# Sheet1.net
KiCad netlist of a schematic drawn in Altium Designer
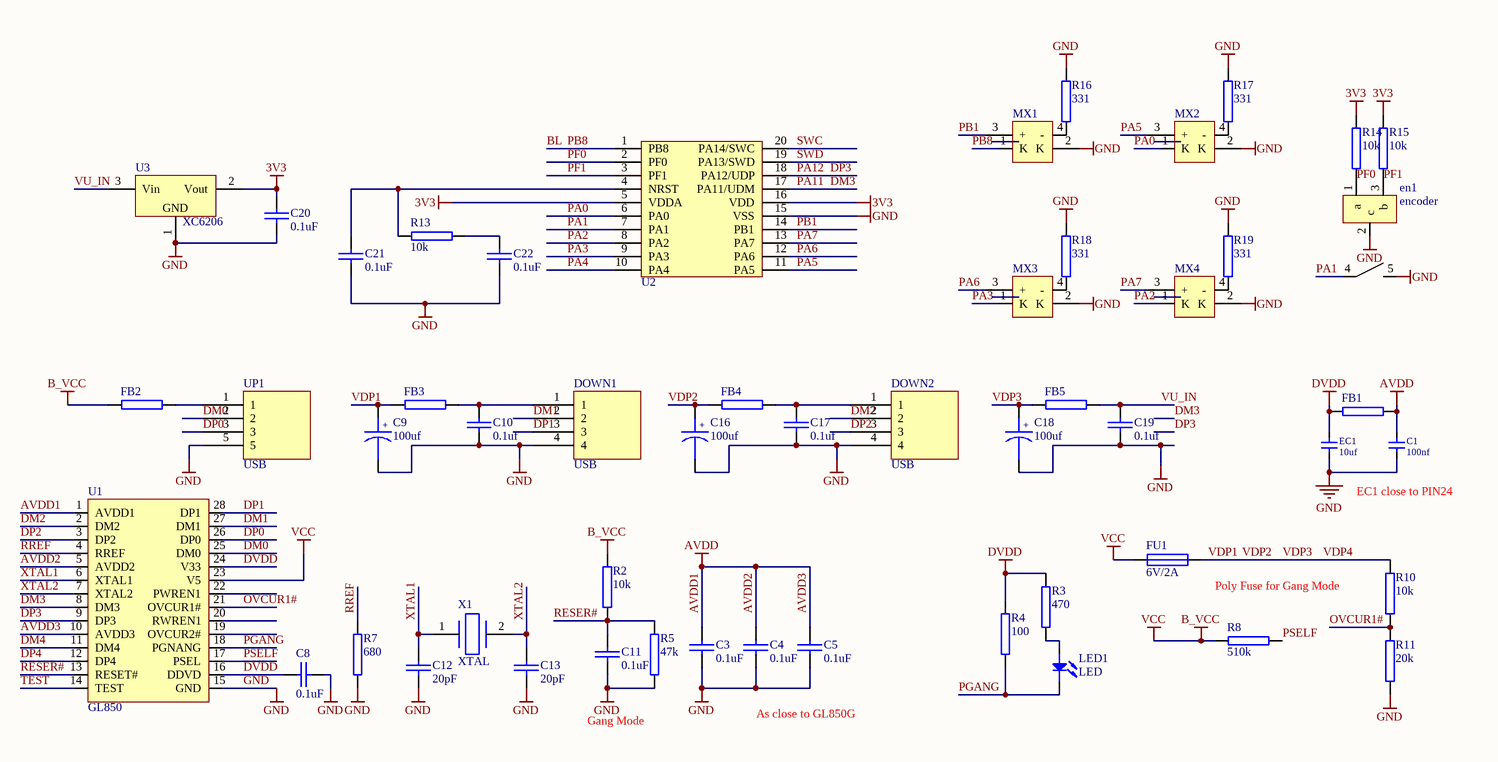
[diagram p0: Sheet1.SchDoc]

(export (version "E")
  (design (tool "Eeschema 10.0.6"))
  (components
    (comp (ref "C1")
      (value "100nf")
      (footprint "C0805")
      (description "Capacitor")
      (libsource (lib "lflj_com") (part "CAP"))
    )
    (comp (ref "C3") (value "0.1uF") (footprint "C0805") (libsource (lib "常用元件库") (part "CAP")))
    (comp (ref "C4") (value "0.1uF") (footprint "C0805") (libsource (lib "常用元件库") (part "CAP")))
    (comp (ref "C5") (value "0.1uF") (footprint "C0805") (libsource (lib "常用元件库") (part "CAP")))
    (comp (ref "C8") (value "0.1uF") (footprint "C0805") (libsource (lib "常用元件库") (part "CAP")))
    (comp (ref "C9")
      (value "100uf")
      (footprint "C0805")
      (description "Capacitor")
      (libsource (lib "元件库") (part "电解电容"))
    )
    (comp (ref "C10") (value "0.1uf") (footprint "C0805") (libsource (lib "元件库") (part "CAP")))
    (comp (ref "C11") (value "0.1uF") (footprint "C0805") (libsource (lib "常用元件库") (part "CAP")))
    (comp (ref "C12") (value "20pF") (footprint "C0805") (libsource (lib "常用元件库") (part "CAP")))
    (comp (ref "C13") (value "20pF") (footprint "C0805") (libsource (lib "常用元件库") (part "CAP")))
    (comp (ref "C16")
      (value "100uf")
      (footprint "C0805")
      (description "Capacitor")
      (libsource (lib "元件库") (part "电解电容"))
    )
    (comp (ref "C17") (value "0.1uf") (footprint "C0805") (libsource (lib "元件库") (part "CAP")))
    (comp (ref "C18")
      (value "100uf")
      (footprint "C0805")
      (description "Capacitor")
      (libsource (lib "元件库") (part "电解电容"))
    )
    (comp (ref "C19") (value "0.1uf") (footprint "C0805") (libsource (lib "元件库") (part "CAP")))
    (comp (ref "C20") (value "0.1uF") (footprint "C0805") (libsource (lib "常用元件库") (part "CAP")))
    (comp (ref "C21") (value "0.1uF") (footprint "C0805") (libsource (lib "常用元件库") (part "CAP")))
    (comp (ref "C22") (value "0.1uF") (footprint "C0805") (libsource (lib "常用元件库") (part "CAP")))
    (comp (ref "DOWN1")
      (value "USB")
      (footprint "USB-A/S_D")
      (description "4 Pin Header")
      (libsource (lib "元件库") (part "USB"))
    )
    (comp (ref "DOWN2")
      (value "USB")
      (footprint "USB-A/S_D")
      (description "4 Pin Header")
      (libsource (lib "元件库") (part "USB"))
    )
    (comp (ref "EC1")
      (value "10uf")
      (footprint "C0805")
      (description "Capacitor")
      (libsource (lib "lflj_com") (part "CAP"))
    )
    (comp (ref "en1")
      (value "encoder")
      (footprint "RES ADJ-EC12")
      (libsource (lib "KeyBoard(1)") (part "encoder"))
    )
    (comp (ref "FB1") (value "~") (footprint "R0805") (libsource (lib "元件库") (part "R")))
    (comp (ref "FB2") (value "~") (footprint "R0805") (libsource (lib "元件库") (part "R")))
    (comp (ref "FB3") (value "~") (footprint "R0805") (libsource (lib "元件库") (part "R")))
    (comp (ref "FB4") (value "~") (footprint "R0805") (libsource (lib "元件库") (part "R")))
    (comp (ref "FB5") (value "~") (footprint "R0805") (libsource (lib "元件库") (part "R")))
    (comp (ref "FU1") (value "6V/2A") (footprint "FUSE-F1210") (libsource (lib "元件库") (part "FUSE")))
    (comp (ref "LED1") (value "LED") (footprint "LED0805") (libsource (lib "常用元件库") (part "LED")))
    (comp (ref "MX1") (value "~") (footprint "MX_SW-5") (libsource (lib "KeyBoard(1)") (part "MX_SW-7")))
    (comp (ref "MX2") (value "~") (footprint "MX_SW-5") (libsource (lib "KeyBoard(1)") (part "MX_SW-7")))
    (comp (ref "MX3") (value "~") (footprint "MX_SW-5") (libsource (lib "KeyBoard(1)") (part "MX_SW-7")))
    (comp (ref "MX4") (value "~") (footprint "MX_SW-5") (libsource (lib "KeyBoard(1)") (part "MX_SW-7")))
    (comp (ref "R2") (value "10k") (footprint "R0805") (libsource (lib "常用元件库") (part "RES")))
    (comp (ref "R3") (value "470") (footprint "R0805") (libsource (lib "常用元件库") (part "RES")))
    (comp (ref "R4") (value "100") (footprint "R0805") (libsource (lib "常用元件库") (part "RES")))
    (comp (ref "R5") (value "47k") (footprint "R0805") (libsource (lib "常用元件库") (part "RES")))
    (comp (ref "R7") (value "680") (footprint "R0805") (libsource (lib "常用元件库") (part "RES")))
    (comp (ref "R8") (value "510k") (footprint "R0805") (libsource (lib "元件库") (part "R")))
    (comp (ref "R10") (value "10k") (footprint "R0805") (libsource (lib "元件库") (part "R")))
    (comp (ref "R11") (value "20k") (footprint "R0805") (libsource (lib "元件库") (part "R")))
    (comp (ref "R13") (value "10k") (footprint "R0805") (libsource (lib "常用元件库") (part "RES")))
    (comp (ref "R14") (value "10k") (footprint "R0805") (libsource (lib "常用元件库") (part "RES")))
    (comp (ref "R15") (value "10k") (footprint "R0805") (libsource (lib "常用元件库") (part "RES")))
    (comp (ref "R16") (value "331") (footprint "R0805") (libsource (lib "KeyBoard(1)") (part "R")))
    (comp (ref "R17") (value "331") (footprint "R0805") (libsource (lib "KeyBoard(1)") (part "R")))
    (comp (ref "R18") (value "331") (footprint "R0805") (libsource (lib "KeyBoard(1)") (part "R")))
    (comp (ref "R19") (value "331") (footprint "R0805") (libsource (lib "KeyBoard(1)") (part "R")))
    (comp (ref "U1") (value "GL850") (footprint "SSOP28") (libsource (lib "SCHL") (part "GL850")))
    (comp (ref "U2")
      (value "stm32f042Fx")
      (footprint "TSSOP20")
      (libsource (lib "KeyBoard(1)") (part "stm32f042Fx"))
    )
    (comp (ref "U3") (value "XC6206") (footprint "SOT23-3") (libsource (lib "KeyBoard(1)") (part "XC6206")))
    (comp (ref "UP1")
      (value "USB")
      (footprint "USB-micro_B")
      (description "4 Pin Header")
      (libsource (lib "") (part "USB_1"))
    )
    (comp (ref "X1")
      (value "XTAL")
      (footprint "X5032")
      (description "12M")
      (libsource (lib "元件库") (part "XTAL"))
    )
  )
  (nets
    (net (code "1") (name "/BL") (class "Default")
      (node (ref "MX1") (pin "1") (pinfunction "K_1") (pintype "passive"))
      (node (ref "U2") (pin "1") (pinfunction "PB8_1") (pintype "passive"))
    )
    (net (code "2") (name "/DM0") (class "Default")
      (node (ref "U1") (pin "25") (pinfunction "DM0_25") (pintype "passive"))
      (node (ref "UP1") (pin "2") (pinfunction "2_2") (pintype "passive"))
    )
    (net (code "3") (name "/DM1") (class "Default")
      (node (ref "DOWN1") (pin "2") (pinfunction "2_2") (pintype "passive"))
      (node (ref "U1") (pin "27") (pinfunction "DM1_27") (pintype "passive"))
    )
    (net (code "4") (name "/DM2") (class "Default")
      (node (ref "DOWN2") (pin "2") (pinfunction "2_2") (pintype "passive"))
      (node (ref "U1") (pin "2") (pinfunction "DM2_2") (pintype "passive"))
    )
    (net (code "5") (name "/DM3") (class "Default")
      (node (ref "U1") (pin "8") (pinfunction "DM3_8") (pintype "passive"))
      (node (ref "U2") (pin "17") (pinfunction "PA11/UDM_17") (pintype "passive"))
    )
    (net (code "6") (name "/DM4") (class "Default")
      (node (ref "U1") (pin "11") (pinfunction "DM4_11") (pintype "passive"))
    )
    (net (code "7") (name "/DP0") (class "Default")
      (node (ref "U1") (pin "26") (pinfunction "DP0_26") (pintype "passive"))
      (node (ref "UP1") (pin "3") (pinfunction "3_3") (pintype "passive"))
    )
    (net (code "8") (name "/DP1") (class "Default")
      (node (ref "DOWN1") (pin "3") (pinfunction "3_3") (pintype "passive"))
      (node (ref "U1") (pin "28") (pinfunction "DP1_28") (pintype "passive"))
    )
    (net (code "9") (name "/DP2") (class "Default")
      (node (ref "DOWN2") (pin "3") (pinfunction "3_3") (pintype "passive"))
      (node (ref "U1") (pin "3") (pinfunction "DP2_3") (pintype "passive"))
    )
    (net (code "10") (name "/DP3") (class "Default")
      (node (ref "U1") (pin "9") (pinfunction "DP3_9") (pintype "passive"))
      (node (ref "U2") (pin "18") (pinfunction "PA12/UDP_18") (pintype "passive"))
    )
    (net (code "11") (name "/DP4") (class "Default")
      (node (ref "U1") (pin "12") (pinfunction "DP4_12") (pintype "passive"))
    )
    (net (code "12") (name "/OVCUR1#") (class "Default")
      (node (ref "R10") (pin "1") (pinfunction "1_1") (pintype "passive"))
      (node (ref "R11") (pin "2") (pinfunction "2_2") (pintype "passive"))
      (node (ref "U1") (pin "21") (pinfunction "OVCUR1#_21") (pintype "passive"))
    )
    (net (code "13") (name "/PA0") (class "Default")
      (node (ref "MX2") (pin "1") (pinfunction "K_1") (pintype "passive"))
      (node (ref "U2") (pin "6") (pinfunction "PA0_6") (pintype "passive"))
    )
    (net (code "14") (name "/PA1") (class "Default")
      (node (ref "U2") (pin "7") (pinfunction "PA1_7") (pintype "passive"))
      (node (ref "en1") (pin "4") (pintype "passive"))
    )
    (net (code "15") (name "/PA2") (class "Default")
      (node (ref "MX4") (pin "1") (pinfunction "K_1") (pintype "passive"))
      (node (ref "U2") (pin "8") (pinfunction "PA2_8") (pintype "passive"))
    )
    (net (code "16") (name "/PA3") (class "Default")
      (node (ref "MX3") (pin "1") (pinfunction "K_1") (pintype "passive"))
      (node (ref "U2") (pin "9") (pinfunction "PA3_9") (pintype "passive"))
    )
    (net (code "17") (name "/PA4") (class "Default")
      (node (ref "U2") (pin "10") (pinfunction "PA4_10") (pintype "passive"))
    )
    (net (code "18") (name "/PA5") (class "Default")
      (node (ref "MX2") (pin "3") (pinfunction "+_3") (pintype "passive"))
      (node (ref "U2") (pin "11") (pinfunction "PA5_11") (pintype "passive"))
    )
    (net (code "19") (name "/PA6") (class "Default")
      (node (ref "MX3") (pin "3") (pinfunction "+_3") (pintype "passive"))
      (node (ref "U2") (pin "12") (pinfunction "PA6_12") (pintype "passive"))
    )
    (net (code "20") (name "/PA7") (class "Default")
      (node (ref "MX4") (pin "3") (pinfunction "+_3") (pintype "passive"))
      (node (ref "U2") (pin "13") (pinfunction "PA7_13") (pintype "passive"))
    )
    (net (code "21") (name "/PB1") (class "Default")
      (node (ref "MX1") (pin "3") (pinfunction "+_3") (pintype "passive"))
      (node (ref "U2") (pin "14") (pinfunction "PB1_14") (pintype "passive"))
    )
    (net (code "22") (name "/PF0") (class "Default")
      (node (ref "R14") (pin "1") (pinfunction "1_1") (pintype "passive"))
      (node (ref "U2") (pin "2") (pinfunction "PF0_2") (pintype "passive"))
      (node (ref "en1") (pin "1") (pinfunction "a_1") (pintype "passive"))
    )
    (net (code "23") (name "/PF1") (class "Default")
      (node (ref "R15") (pin "1") (pinfunction "1_1") (pintype "passive"))
      (node (ref "U2") (pin "3") (pinfunction "PF1_3") (pintype "passive"))
      (node (ref "en1") (pin "3") (pinfunction "b_3") (pintype "passive"))
    )
    (net (code "24") (name "/PGANG") (class "Default")
      (node (ref "LED1") (pin "2") (pinfunction "2_2") (pintype "passive"))
      (node (ref "R4") (pin "1") (pinfunction "1_1") (pintype "passive"))
      (node (ref "U1") (pin "18") (pinfunction "PGNANG_18") (pintype "passive"))
    )
    (net (code "25") (name "/PSELF") (class "Default")
      (node (ref "R8") (pin "2") (pinfunction "2_2") (pintype "passive"))
      (node (ref "U1") (pin "17") (pinfunction "PSEL_17") (pintype "passive"))
    )
    (net (code "26") (name "/RESER#") (class "Default")
      (node (ref "C11") (pin "1") (pinfunction "1_1") (pintype "passive"))
      (node (ref "R2") (pin "1") (pinfunction "1_1") (pintype "passive"))
      (node (ref "R5") (pin "1") (pinfunction "1_1") (pintype "passive"))
      (node (ref "U1") (pin "13") (pinfunction "RESET#_13") (pintype "passive"))
    )
    (net (code "27") (name "/RREF") (class "Default")
      (node (ref "R7") (pin "2") (pinfunction "2_2") (pintype "passive"))
      (node (ref "U1") (pin "4") (pinfunction "RREF_4") (pintype "passive"))
    )
    (net (code "28") (name "/SWC") (class "Default")
      (node (ref "U2") (pin "20") (pinfunction "PA14/SWC_20") (pintype "passive"))
    )
    (net (code "29") (name "/SWD") (class "Default")
      (node (ref "U2") (pin "19") (pinfunction "PA13/SWD_19") (pintype "passive"))
    )
    (net (code "30") (name "/TEST") (class "Default")
      (node (ref "U1") (pin "14") (pinfunction "TEST_14") (pintype "passive"))
    )
    (net (code "31") (name "/VDP1") (class "Default")
      (node (ref "C16") (pin "1") (pinfunction "1_1") (pintype "passive"))
      (node (ref "C18") (pin "1") (pinfunction "1_1") (pintype "passive"))
      (node (ref "C9") (pin "1") (pinfunction "1_1") (pintype "passive"))
      (node (ref "FB3") (pin "1") (pinfunction "1_1") (pintype "passive"))
      (node (ref "FB4") (pin "1") (pinfunction "1_1") (pintype "passive"))
      (node (ref "FB5") (pin "1") (pinfunction "1_1") (pintype "passive"))
      (node (ref "FU1") (pin "2") (pinfunction "2_2") (pintype "passive"))
      (node (ref "R10") (pin "2") (pinfunction "2_2") (pintype "passive"))
    )
    (net (code "32") (name "/VU_IN") (class "Default")
      (node (ref "C19") (pin "1") (pinfunction "1_1") (pintype "passive"))
      (node (ref "FB5") (pin "2") (pinfunction "2_2") (pintype "passive"))
      (node (ref "U3") (pin "3") (pinfunction "Vin_3") (pintype "passive"))
    )
    (net (code "33") (name "/XTAL1") (class "Default")
      (node (ref "C12") (pin "2") (pinfunction "2_2") (pintype "passive"))
      (node (ref "U1") (pin "6") (pinfunction "XTAL1_6") (pintype "passive"))
      (node (ref "X1") (pin "1") (pinfunction "1_1") (pintype "passive"))
    )
    (net (code "34") (name "/XTAL2") (class "Default")
      (node (ref "C13") (pin "2") (pinfunction "2_2") (pintype "passive"))
      (node (ref "U1") (pin "7") (pinfunction "XTAL2_7") (pintype "passive"))
      (node (ref "X1") (pin "2") (pinfunction "2_2") (pintype "passive"))
    )
    (net (code "35") (name "3V3") (class "Default")
      (node (ref "C20") (pin "1") (pinfunction "1_1") (pintype "passive"))
      (node (ref "R14") (pin "2") (pinfunction "2_2") (pintype "passive"))
      (node (ref "R15") (pin "2") (pinfunction "2_2") (pintype "passive"))
      (node (ref "U2") (pin "16") (pinfunction "VDD_16") (pintype "passive"))
      (node (ref "U2") (pin "5") (pinfunction "VDDA_5") (pintype "passive"))
      (node (ref "U3") (pin "2") (pinfunction "Vout_2") (pintype "passive"))
    )
    (net (code "36") (name "AVDD") (class "Default")
      (node (ref "C1") (pin "2") (pinfunction "2_2") (pintype "passive"))
      (node (ref "C3") (pin "1") (pinfunction "1_1") (pintype "passive"))
      (node (ref "C4") (pin "1") (pinfunction "1_1") (pintype "passive"))
      (node (ref "C5") (pin "1") (pinfunction "1_1") (pintype "passive"))
      (node (ref "FB1") (pin "2") (pinfunction "2_2") (pintype "passive"))
      (node (ref "U1") (pin "1") (pinfunction "AVDD1_1") (pintype "passive"))
      (node (ref "U1") (pin "10") (pinfunction "AVDD3_10") (pintype "passive"))
      (node (ref "U1") (pin "5") (pinfunction "AVDD2_5") (pintype "passive"))
    )
    (net (code "37") (name "B_VCC") (class "Default")
      (node (ref "FB2") (pin "1") (pinfunction "1_1") (pintype "passive"))
      (node (ref "FU1") (pin "1") (pinfunction "1_1") (pintype "passive"))
      (node (ref "R2") (pin "2") (pinfunction "2_2") (pintype "passive"))
      (node (ref "R8") (pin "1") (pinfunction "1_1") (pintype "passive"))
      (node (ref "U1") (pin "23") (pinfunction "V5_23") (pintype "passive"))
    )
    (net (code "38") (name "DVDD") (class "Default")
      (node (ref "C8") (pin "1") (pinfunction "1_1") (pintype "passive"))
      (node (ref "EC1") (pin "2") (pinfunction "2_2") (pintype "passive"))
      (node (ref "FB1") (pin "1") (pinfunction "1_1") (pintype "passive"))
      (node (ref "R3") (pin "2") (pinfunction "2_2") (pintype "passive"))
      (node (ref "R4") (pin "2") (pinfunction "2_2") (pintype "passive"))
      (node (ref "U1") (pin "16") (pinfunction "DDVD_16") (pintype "passive"))
      (node (ref "U1") (pin "24") (pinfunction "V33_24") (pintype "passive"))
    )
    (net (code "39") (name "GND") (class "Default")
      (node (ref "C1") (pin "1") (pinfunction "1_1") (pintype "passive"))
      (node (ref "C10") (pin "2") (pinfunction "2_2") (pintype "passive"))
      (node (ref "C11") (pin "2") (pinfunction "2_2") (pintype "passive"))
      (node (ref "C12") (pin "1") (pinfunction "1_1") (pintype "passive"))
      (node (ref "C13") (pin "1") (pinfunction "1_1") (pintype "passive"))
      (node (ref "C16") (pin "2") (pinfunction "2_2") (pintype "passive"))
      (node (ref "C17") (pin "2") (pinfunction "2_2") (pintype "passive"))
      (node (ref "C18") (pin "2") (pinfunction "2_2") (pintype "passive"))
      (node (ref "C19") (pin "2") (pinfunction "2_2") (pintype "passive"))
      (node (ref "C20") (pin "2") (pinfunction "2_2") (pintype "passive"))
      (node (ref "C21") (pin "1") (pinfunction "1_1") (pintype "passive"))
      (node (ref "C22") (pin "1") (pinfunction "1_1") (pintype "passive"))
      (node (ref "C3") (pin "2") (pinfunction "2_2") (pintype "passive"))
      (node (ref "C4") (pin "2") (pinfunction "2_2") (pintype "passive"))
      (node (ref "C5") (pin "2") (pinfunction "2_2") (pintype "passive"))
      (node (ref "C8") (pin "2") (pinfunction "2_2") (pintype "passive"))
      (node (ref "C9") (pin "2") (pinfunction "2_2") (pintype "passive"))
      (node (ref "DOWN1") (pin "4") (pinfunction "4_4") (pintype "passive"))
      (node (ref "DOWN2") (pin "4") (pinfunction "4_4") (pintype "passive"))
      (node (ref "EC1") (pin "1") (pinfunction "1_1") (pintype "passive"))
      (node (ref "MX1") (pin "2") (pinfunction "K_2") (pintype "passive"))
      (node (ref "MX2") (pin "2") (pinfunction "K_2") (pintype "passive"))
      (node (ref "MX3") (pin "2") (pinfunction "K_2") (pintype "passive"))
      (node (ref "MX4") (pin "2") (pinfunction "K_2") (pintype "passive"))
      (node (ref "R11") (pin "1") (pinfunction "1_1") (pintype "passive"))
      (node (ref "R16") (pin "2") (pinfunction "2_2") (pintype "passive"))
      (node (ref "R17") (pin "2") (pinfunction "2_2") (pintype "passive"))
      (node (ref "R18") (pin "2") (pinfunction "2_2") (pintype "passive"))
      (node (ref "R19") (pin "2") (pinfunction "2_2") (pintype "passive"))
      (node (ref "R5") (pin "2") (pinfunction "2_2") (pintype "passive"))
      (node (ref "R7") (pin "1") (pinfunction "1_1") (pintype "passive"))
      (node (ref "U1") (pin "15") (pinfunction "GND_15") (pintype "passive"))
      (node (ref "U2") (pin "15") (pinfunction "VSS_15") (pintype "passive"))
      (node (ref "U3") (pin "1") (pinfunction "GND_1") (pintype "passive"))
      (node (ref "UP1") (pin "5") (pinfunction "5_5") (pintype "passive"))
      (node (ref "en1") (pin "2") (pinfunction "c_2") (pintype "passive"))
      (node (ref "en1") (pin "5") (pintype "passive"))
    )
    (net (code "40") (name "Net-(C10-Pad1)") (class "Default")
      (node (ref "C10") (pin "1") (pinfunction "1_1") (pintype "passive"))
      (node (ref "DOWN1") (pin "1") (pinfunction "1_1") (pintype "passive"))
      (node (ref "FB3") (pin "2") (pinfunction "2_2") (pintype "passive"))
    )
    (net (code "41") (name "Net-(C17-Pad1)") (class "Default")
      (node (ref "C17") (pin "1") (pinfunction "1_1") (pintype "passive"))
      (node (ref "DOWN2") (pin "1") (pinfunction "1_1") (pintype "passive"))
      (node (ref "FB4") (pin "2") (pinfunction "2_2") (pintype "passive"))
    )
    (net (code "42") (name "Net-(C22-Pad2)") (class "Default")
      (node (ref "C22") (pin "2") (pinfunction "2_2") (pintype "passive"))
      (node (ref "R13") (pin "2") (pinfunction "2_2") (pintype "passive"))
    )
    (net (code "43") (name "Net-(FB2-Pad2)") (class "Default")
      (node (ref "FB2") (pin "2") (pinfunction "2_2") (pintype "passive"))
      (node (ref "UP1") (pin "1") (pinfunction "1_1") (pintype "passive"))
    )
    (net (code "44") (name "Net-(LED1-Pad1)") (class "Default")
      (node (ref "LED1") (pin "1") (pinfunction "1_1") (pintype "passive"))
      (node (ref "R3") (pin "1") (pinfunction "1_1") (pintype "passive"))
    )
    (net (code "45") (name "Net-(MX1--)") (class "Default")
      (node (ref "MX1") (pin "4") (pinfunction "-_4") (pintype "passive"))
      (node (ref "R16") (pin "1") (pinfunction "1_1") (pintype "passive"))
    )
    (net (code "46") (name "Net-(MX2--)") (class "Default")
      (node (ref "MX2") (pin "4") (pinfunction "-_4") (pintype "passive"))
      (node (ref "R17") (pin "1") (pinfunction "1_1") (pintype "passive"))
    )
    (net (code "47") (name "Net-(MX3--)") (class "Default")
      (node (ref "MX3") (pin "4") (pinfunction "-_4") (pintype "passive"))
      (node (ref "R18") (pin "1") (pinfunction "1_1") (pintype "passive"))
    )
    (net (code "48") (name "Net-(MX4--)") (class "Default")
      (node (ref "MX4") (pin "4") (pinfunction "-_4") (pintype "passive"))
      (node (ref "R19") (pin "1") (pinfunction "1_1") (pintype "passive"))
    )
    (net (code "49") (name "Net-(U2-NRST)") (class "Default")
      (node (ref "C21") (pin "2") (pinfunction "2_2") (pintype "passive"))
      (node (ref "R13") (pin "1") (pinfunction "1_1") (pintype "passive"))
      (node (ref "U2") (pin "4") (pinfunction "NRST_4") (pintype "passive"))
    )
    (net (code "50") (name "unconnected-(U1-OVCUR2#-Pad19)") (class "Default")
      (node (ref "U1") (pin "19") (pinfunction "OVCUR2#_19") (pintype "passive"))
    )
    (net (code "51") (name "unconnected-(U1-PWREN1-Pad22)") (class "Default")
      (node (ref "U1") (pin "22") (pinfunction "PWREN1_22") (pintype "passive"))
    )
    (net (code "52") (name "unconnected-(U1-RWREN1-Pad20)") (class "Default")
      (node (ref "U1") (pin "20") (pinfunction "RWREN1_20") (pintype "passive"))
    )
  )
)
